# pa_only_1800.net
KiCad netlist of a schematic drawn in EAGLE
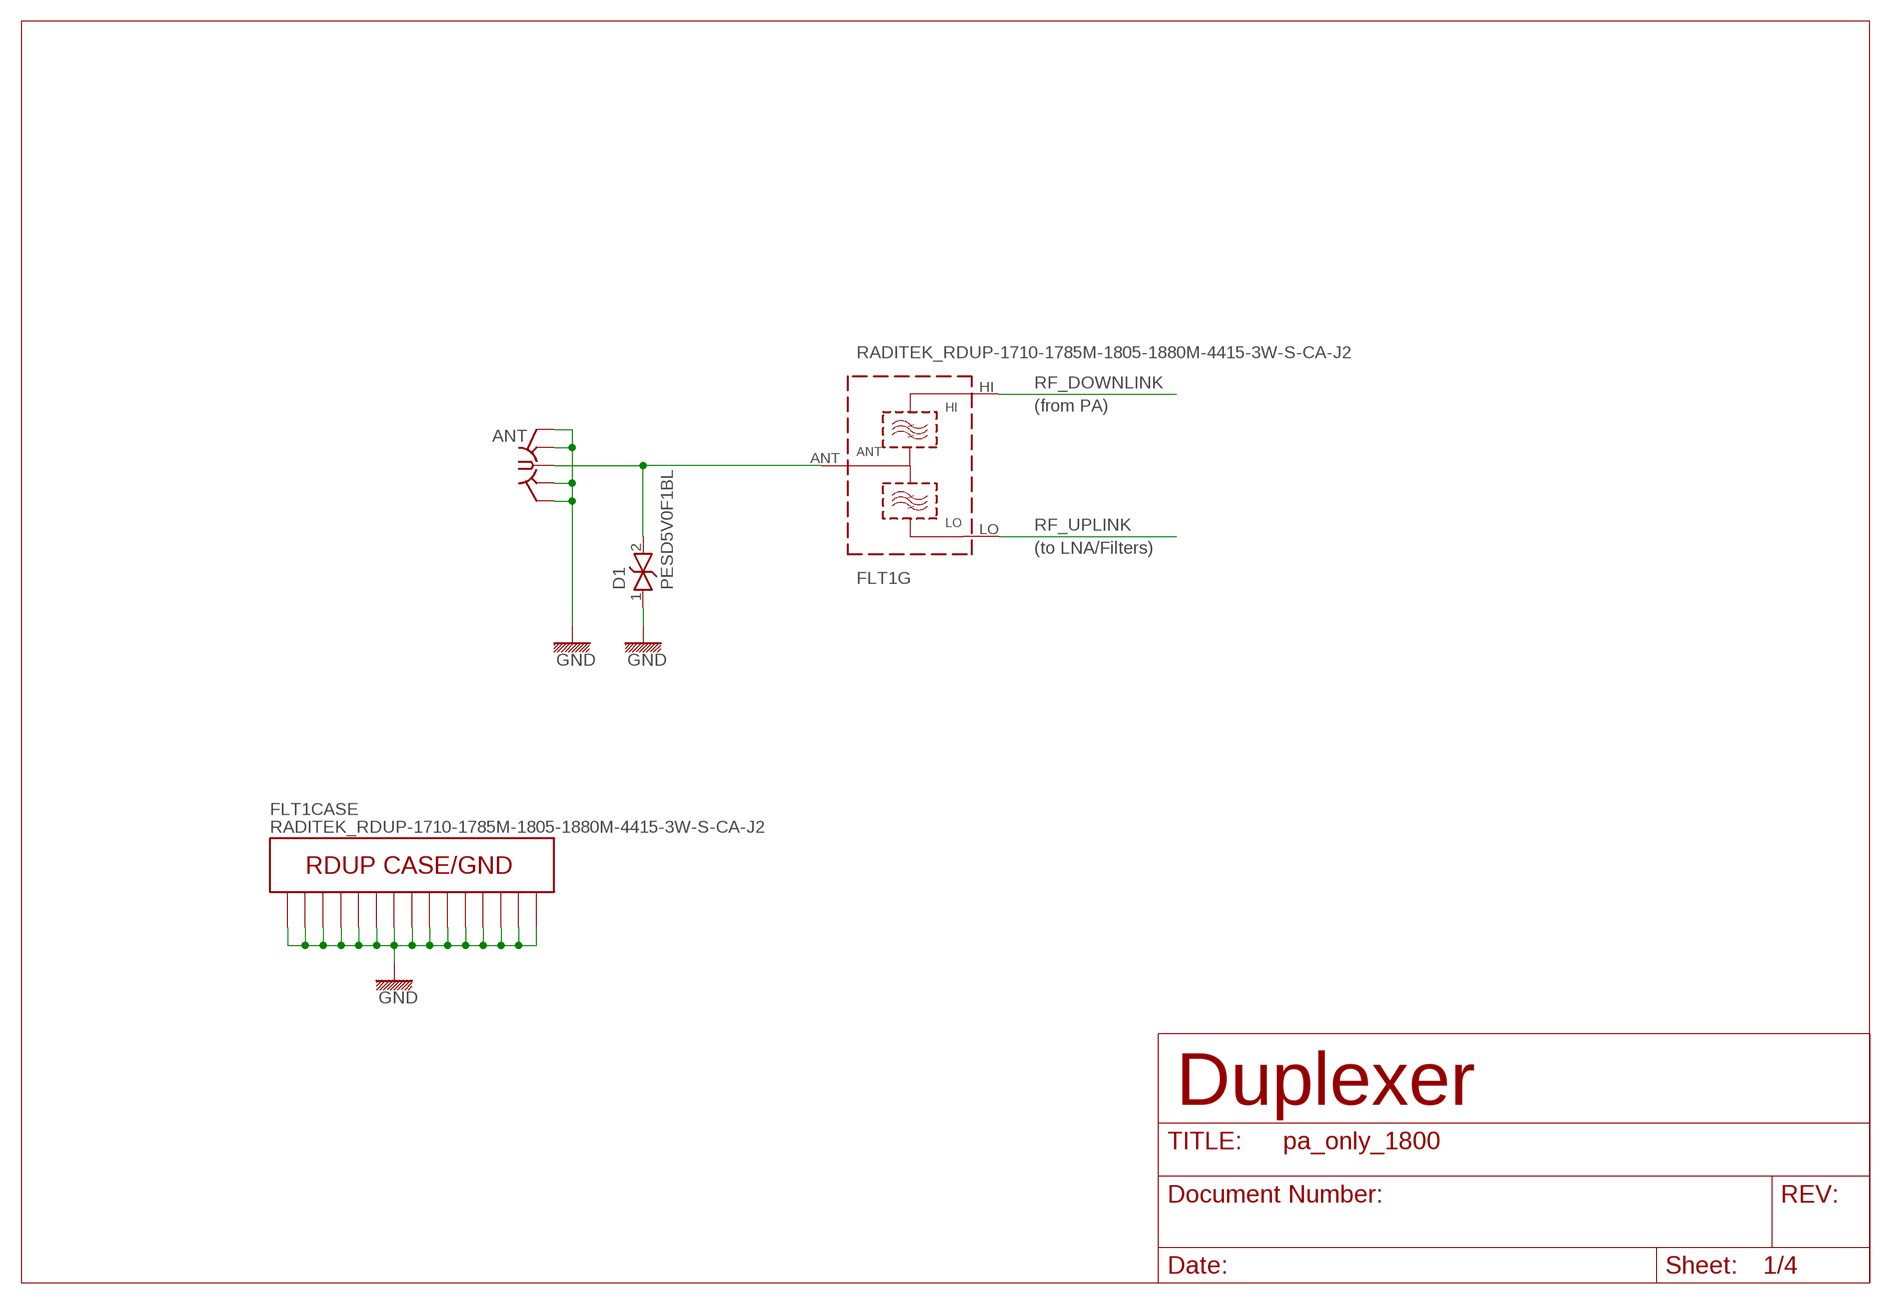
[diagram p0: schematic, sheet 1]
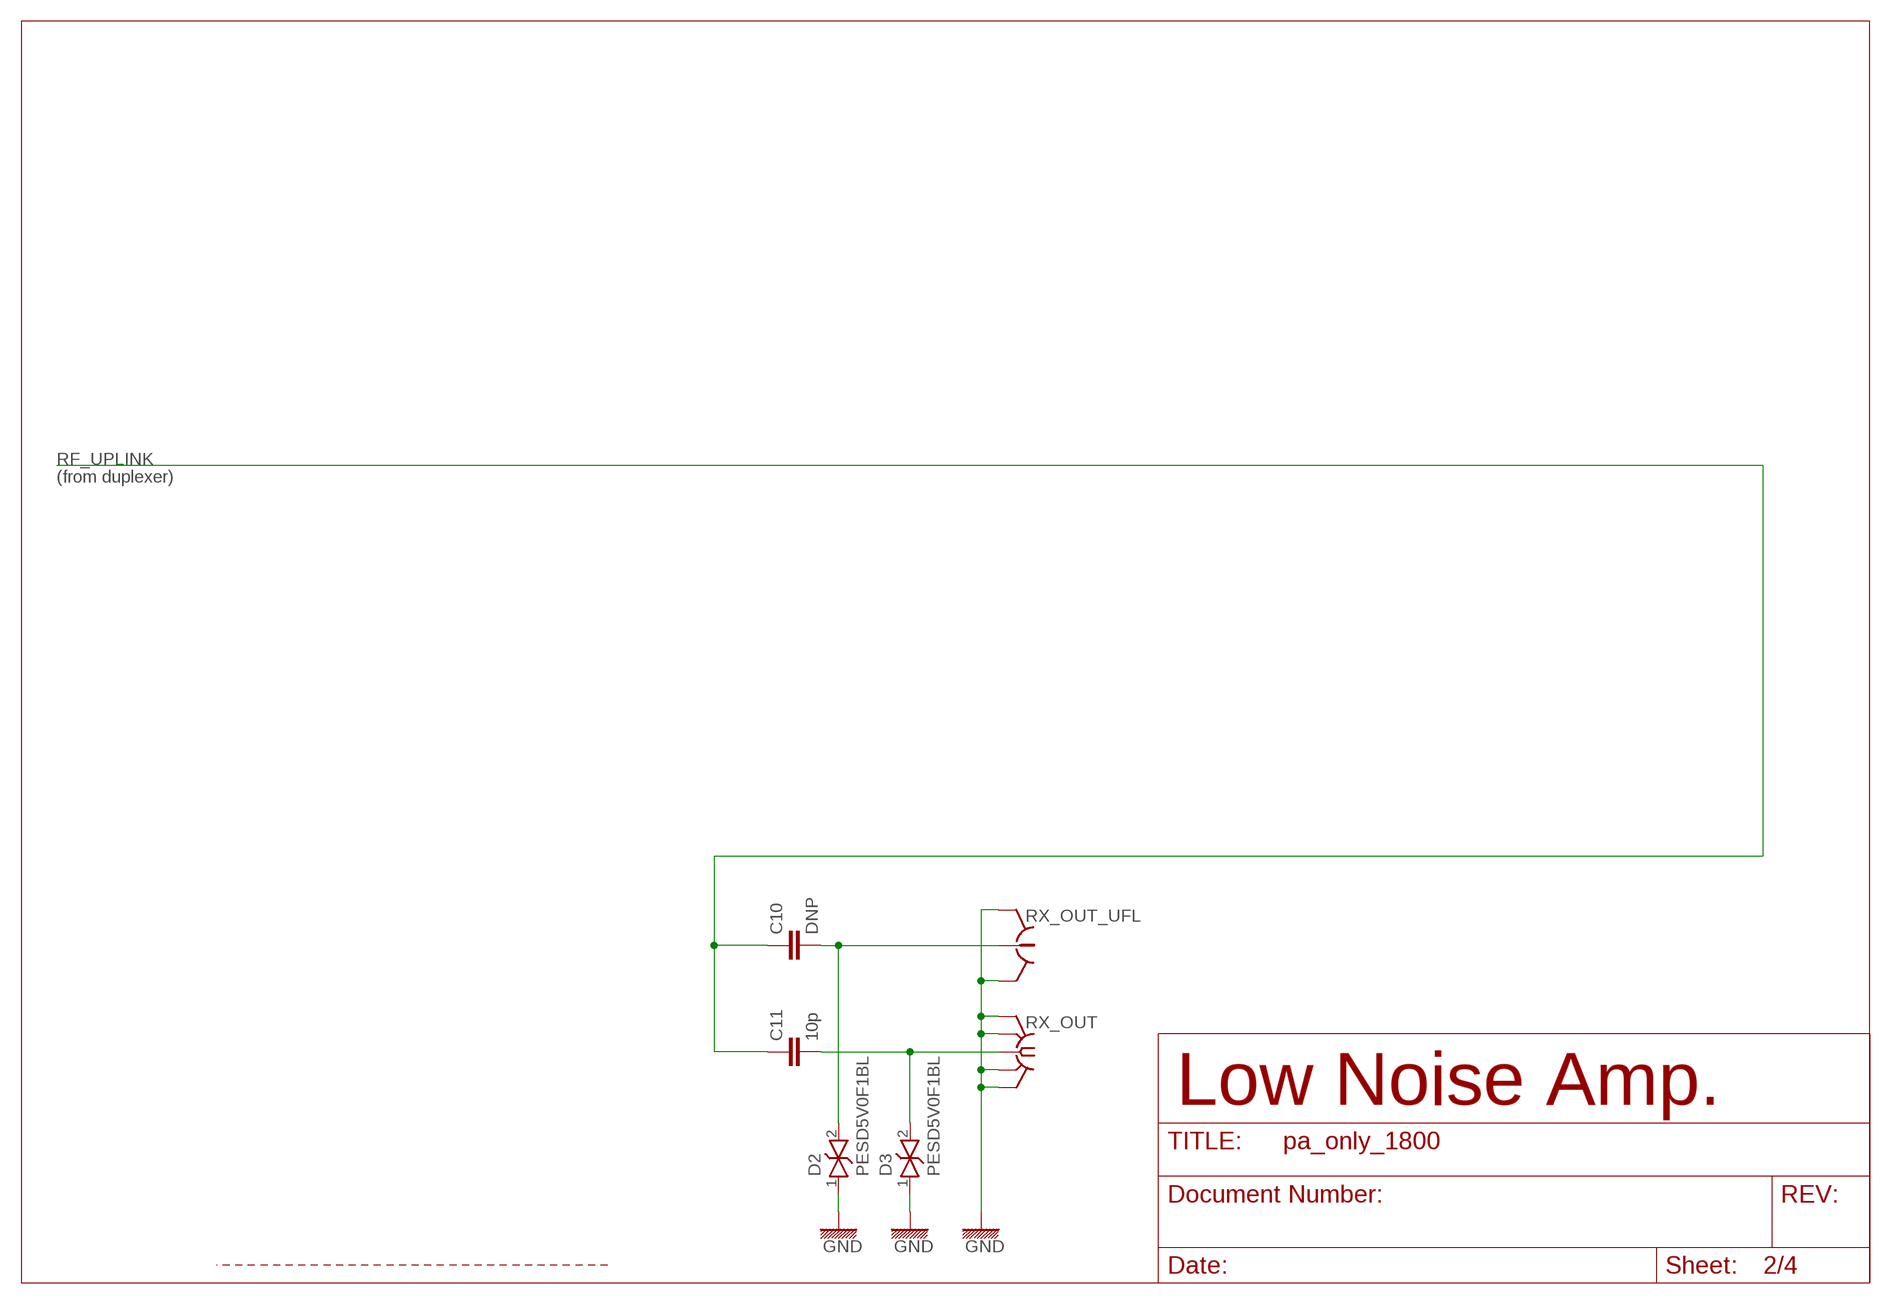
[diagram p1: schematic, sheet 2]
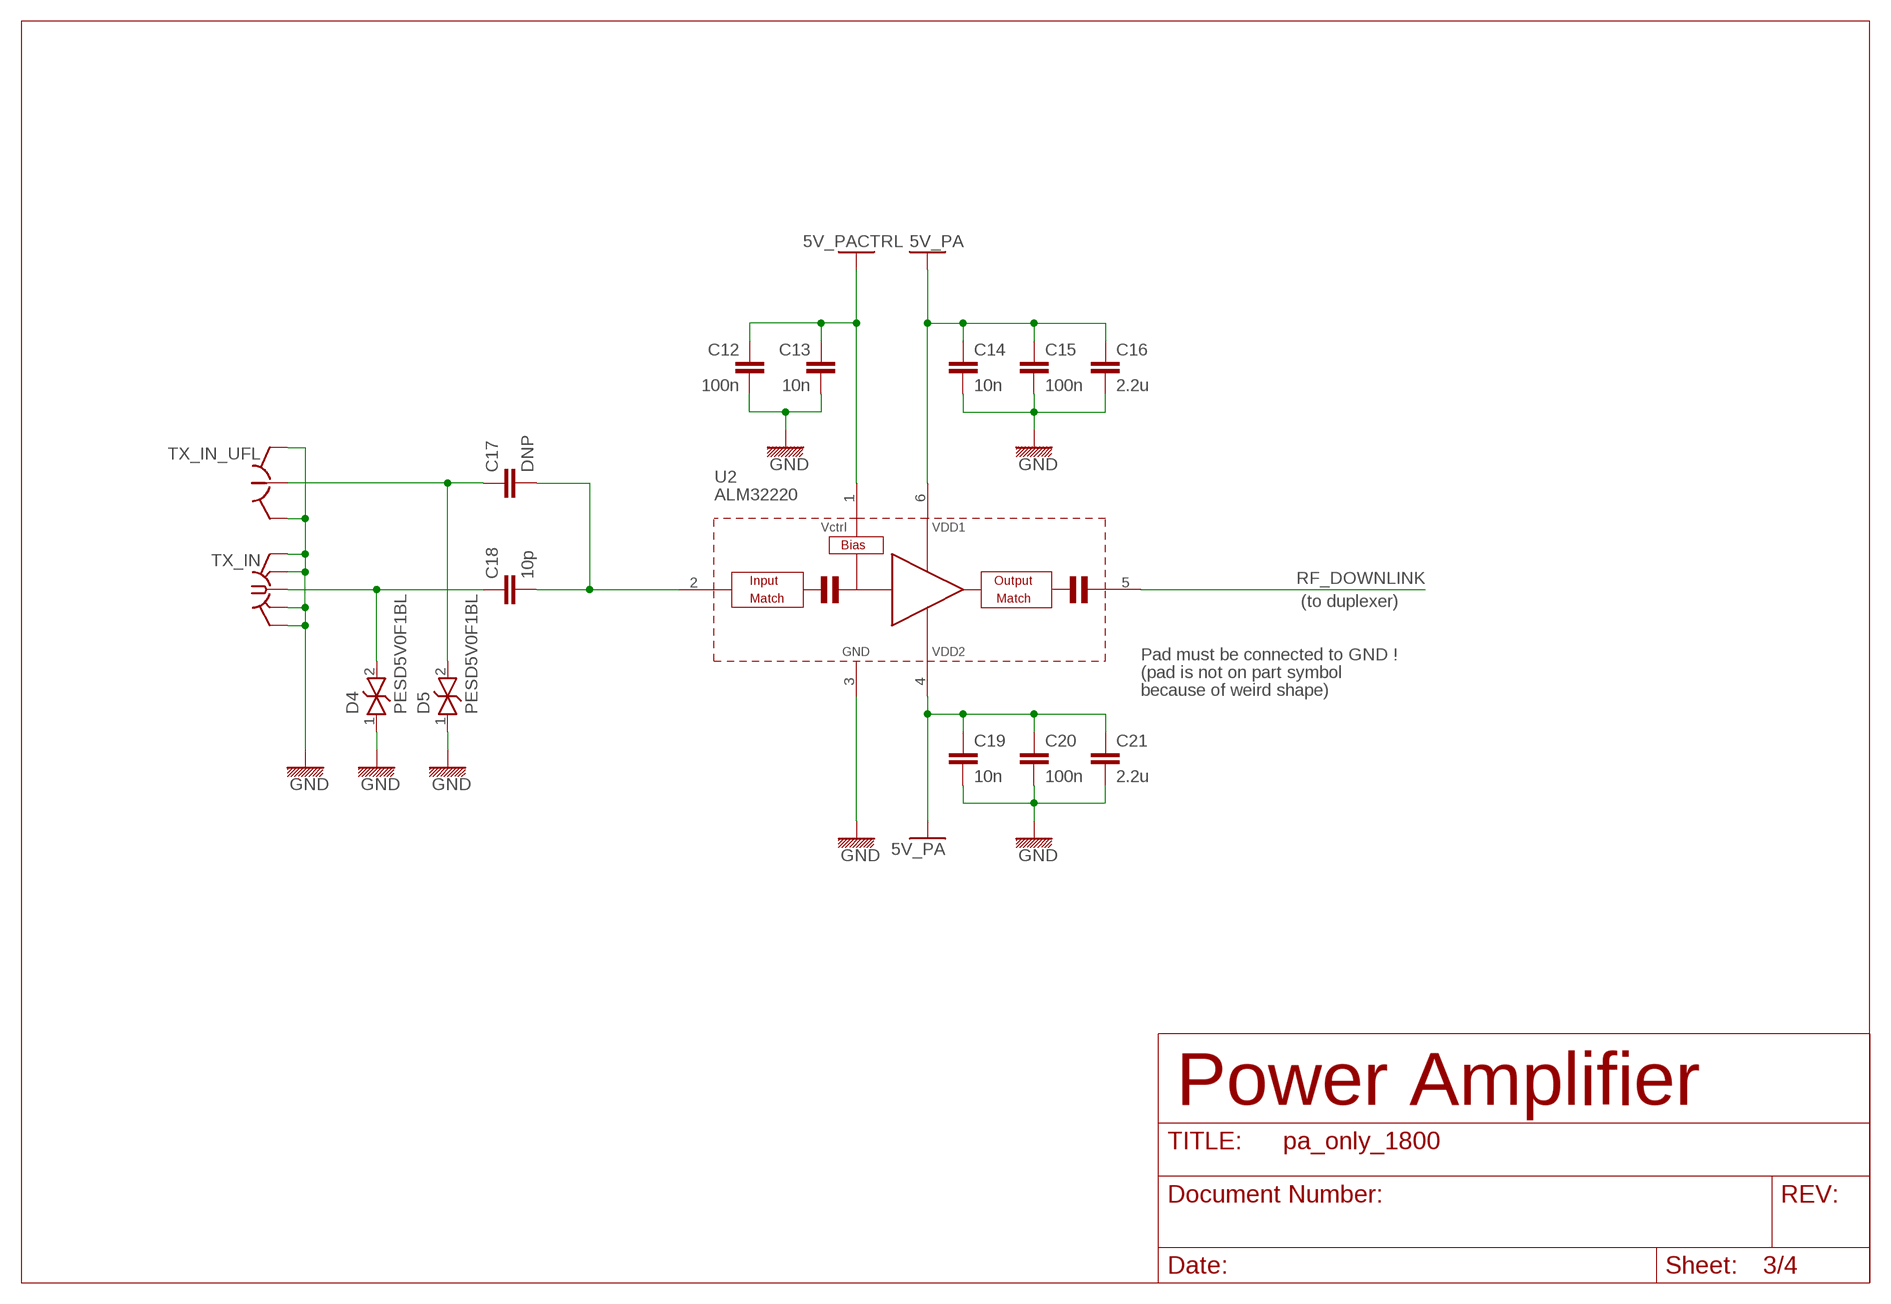
[diagram p2: schematic, sheet 3]
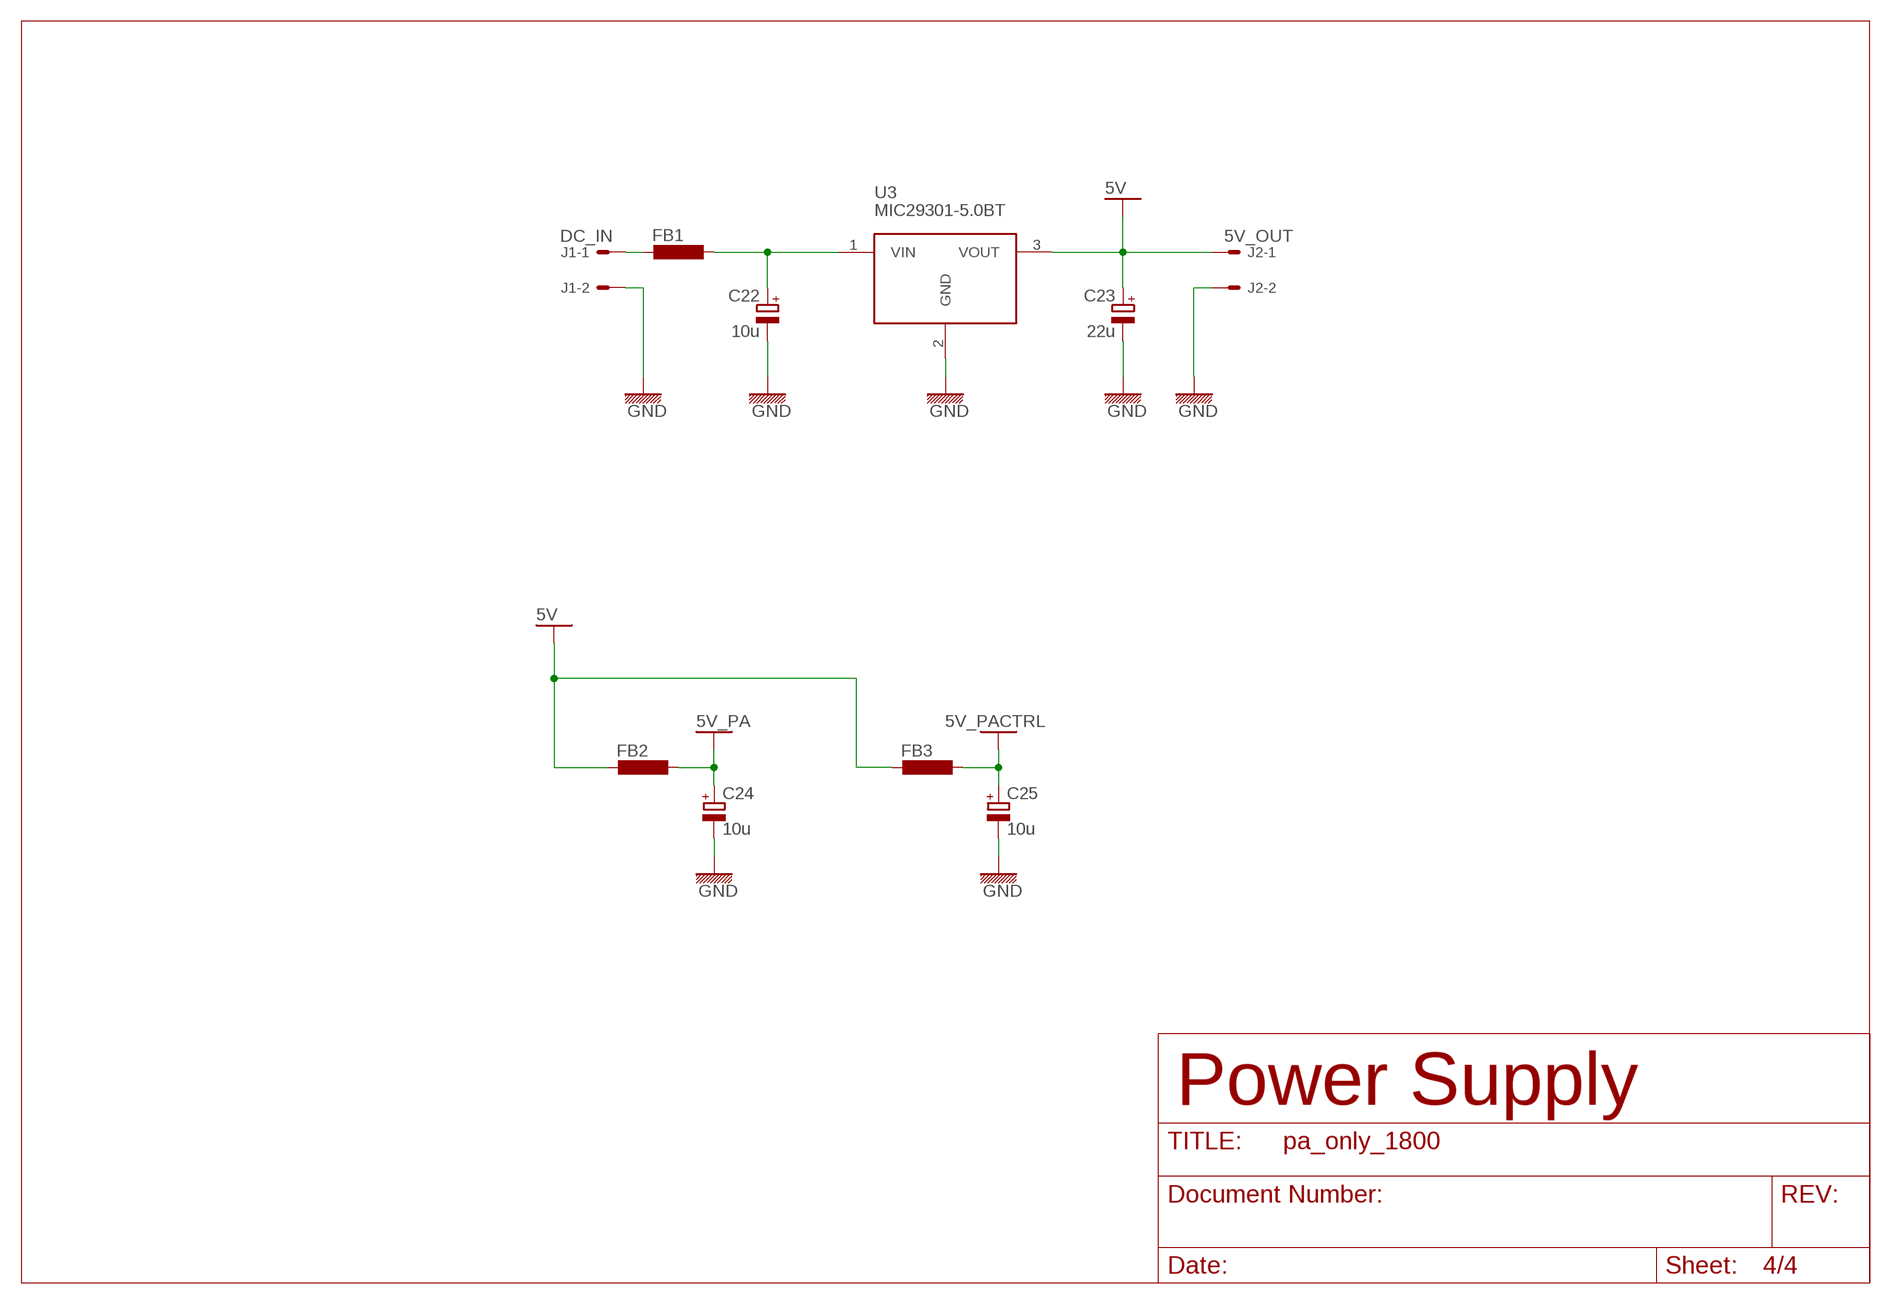
[diagram p3: schematic, sheet 4]

(export (version "E")
  (design (tool "Eeschema 10.0.6"))
  (components
    (comp (ref "ANT")
      (value "SMA-F-S-TH")
      (footprint "eagle-import:SMA-F-S-TH")
      (libsource (lib "eagle-import") (part "SMA-F-S-TH"))
    )
    (comp (ref "D1")
      (value "PESD5V0F1BL")
      (footprint "eagle-import:SOD882")
      (libsource (lib "eagle-import") (part "D_ESD_SOD882"))
    )
    (comp (ref "FLT1")
      (value "RADITEK_RDUP-1710-1785M-1805-1880M-4415-3W-S-CA-J2")
      (footprint "eagle-import:RADITEK_RDUP_4415")
      (libsource (lib "eagle-import") (part "RADITEK_RDUP-1710-1785M-1805-1880M-4415-3W-S-CA-J2"))
    )
    (comp (ref "C22")
      (value "10u")
      (footprint "eagle-import:SMC_A")
      (libsource (lib "eagle-import") (part "CPOL-EUSMCA"))
    )
    (comp (ref "C23")
      (value "22u")
      (footprint "eagle-import:SMC_A")
      (libsource (lib "eagle-import") (part "CPOL-EUSMCA"))
    )
    (comp (ref "C24")
      (value "10u")
      (footprint "eagle-import:SMC_A")
      (libsource (lib "eagle-import") (part "CPOL-EUSMCA"))
    )
    (comp (ref "C25")
      (value "10u")
      (footprint "eagle-import:SMC_A")
      (libsource (lib "eagle-import") (part "CPOL-EUSMCA"))
    )
    (comp (ref "FB1")
      (value "FBEAD_1206")
      (footprint "eagle-import:1206")
      (libsource (lib "eagle-import") (part "FBEAD_1206"))
    )
    (comp (ref "FB2")
      (value "FBEAD_1206")
      (footprint "eagle-import:1206")
      (libsource (lib "eagle-import") (part "FBEAD_1206"))
    )
    (comp (ref "FB3")
      (value "FBEAD_0603")
      (footprint "eagle-import:0603")
      (libsource (lib "eagle-import") (part "FBEAD_0603"))
    )
    (comp (ref "J1")
      (value "DC_IN")
      (footprint "eagle-import:6410-02")
      (libsource (lib "eagle-import") (part "22-?-0227-2021"))
    )
    (comp (ref "J2")
      (value "5V_OUT")
      (footprint "eagle-import:6410-02")
      (fields (field (name "OC_FARNELL") "unknown") (field (name "OC_NEWARK") "unknown"))
      (libsource (lib "eagle-import") (part "22-?-0227-2021"))
    )
    (comp (ref "U3")
      (value "MIC29301-5.0BT")
      (footprint "eagle-import:TO220BV")
      (libsource (lib "eagle-import") (part "MIC29XXX-FIX_WT_TO220BV"))
    )
    (comp (ref "C10")
      (value "DNP")
      (footprint "eagle-import:0603")
      (libsource (lib "eagle-import") (part "C-EU_0603"))
    )
    (comp (ref "C11")
      (value "10p")
      (footprint "eagle-import:0603")
      (libsource (lib "eagle-import") (part "C-EU_0603"))
    )
    (comp (ref "D2")
      (value "PESD5V0F1BL")
      (footprint "eagle-import:SOD882")
      (libsource (lib "eagle-import") (part "D_ESD_SOD882"))
    )
    (comp (ref "D3")
      (value "PESD5V0F1BL")
      (footprint "eagle-import:SOD882")
      (libsource (lib "eagle-import") (part "D_ESD_SOD882"))
    )
    (comp (ref "RX_OUT")
      (value "SMA-F-S-TH")
      (footprint "eagle-import:SMA-F-S-TH")
      (libsource (lib "eagle-import") (part "SMA-F-S-TH"))
    )
    (comp (ref "RX_OUT_UFL")
      (value "HRS_UFL")
      (footprint "eagle-import:HRS_UFL")
      (libsource (lib "eagle-import") (part "HRS_UFL"))
    )
    (comp (ref "C12")
      (value "100n")
      (footprint "eagle-import:0603")
      (libsource (lib "eagle-import") (part "C-EU_0603"))
    )
    (comp (ref "C13")
      (value "10n")
      (footprint "eagle-import:0603")
      (libsource (lib "eagle-import") (part "C-EU_0603"))
    )
    (comp (ref "C14")
      (value "10n")
      (footprint "eagle-import:0603")
      (libsource (lib "eagle-import") (part "C-EU_0603"))
    )
    (comp (ref "C15")
      (value "100n")
      (footprint "eagle-import:0603")
      (libsource (lib "eagle-import") (part "C-EU_0603"))
    )
    (comp (ref "C16")
      (value "2.2u")
      (footprint "eagle-import:0805")
      (libsource (lib "eagle-import") (part "C-EU_0805"))
    )
    (comp (ref "C17")
      (value "DNP")
      (footprint "eagle-import:0603")
      (libsource (lib "eagle-import") (part "C-EU_0603"))
    )
    (comp (ref "C18")
      (value "10p")
      (footprint "eagle-import:0603")
      (libsource (lib "eagle-import") (part "C-EU_0603"))
    )
    (comp (ref "C19")
      (value "10n")
      (footprint "eagle-import:0603")
      (libsource (lib "eagle-import") (part "C-EU_0603"))
    )
    (comp (ref "C20")
      (value "100n")
      (footprint "eagle-import:0603")
      (libsource (lib "eagle-import") (part "C-EU_0603"))
    )
    (comp (ref "C21")
      (value "2.2u")
      (footprint "eagle-import:0805")
      (libsource (lib "eagle-import") (part "C-EU_0805"))
    )
    (comp (ref "D4")
      (value "PESD5V0F1BL")
      (footprint "eagle-import:SOD882")
      (libsource (lib "eagle-import") (part "D_ESD_SOD882"))
    )
    (comp (ref "D5")
      (value "PESD5V0F1BL")
      (footprint "eagle-import:SOD882")
      (libsource (lib "eagle-import") (part "D_ESD_SOD882"))
    )
    (comp (ref "TX_IN")
      (value "SMA-F-S-TH")
      (footprint "eagle-import:SMA-F-S-TH")
      (libsource (lib "eagle-import") (part "SMA-F-S-TH"))
    )
    (comp (ref "TX_IN_UFL")
      (value "HRS_UFL")
      (footprint "eagle-import:HRS_UFL")
      (libsource (lib "eagle-import") (part "HRS_UFL"))
    )
    (comp (ref "U2")
      (value "ALM32220")
      (footprint "eagle-import:ALM32X20")
      (libsource (lib "eagle-import") (part "ALM32220"))
    )
  )
  (nets
    (net (code "1") (name "5V") (class "Default")
      (node (ref "C23") (pin "+") (pinfunction "+_+") (pintype "passive"))
      (node (ref "FB2") (pin "1") (pinfunction "1_1") (pintype "passive"))
      (node (ref "FB3") (pin "1") (pinfunction "1_1") (pintype "passive"))
      (node (ref "J2") (pin "1") (pinfunction "S_1") (pintype "passive"))
      (node (ref "U3") (pin "3") (pinfunction "VOUT_3") (pintype "power_in"))
    )
    (net (code "2") (name "5V_PA") (class "Default")
      (node (ref "C14") (pin "1") (pinfunction "1_1") (pintype "passive"))
      (node (ref "C15") (pin "1") (pinfunction "1_1") (pintype "passive"))
      (node (ref "C16") (pin "1") (pinfunction "1_1") (pintype "passive"))
      (node (ref "C19") (pin "1") (pinfunction "1_1") (pintype "passive"))
      (node (ref "C20") (pin "1") (pinfunction "1_1") (pintype "passive"))
      (node (ref "C21") (pin "1") (pinfunction "1_1") (pintype "passive"))
      (node (ref "C24") (pin "+") (pinfunction "+_+") (pintype "passive"))
      (node (ref "FB2") (pin "2") (pinfunction "2_2") (pintype "passive"))
      (node (ref "U2") (pin "4") (pinfunction "VDD2_4") (pintype "power_in"))
      (node (ref "U2") (pin "6") (pinfunction "VDD1_6") (pintype "power_in"))
    )
    (net (code "3") (name "5V_PACTRL") (class "Default")
      (node (ref "C12") (pin "1") (pinfunction "1_1") (pintype "passive"))
      (node (ref "C13") (pin "1") (pinfunction "1_1") (pintype "passive"))
      (node (ref "C25") (pin "+") (pinfunction "+_+") (pintype "passive"))
      (node (ref "FB3") (pin "2") (pinfunction "2_2") (pintype "passive"))
      (node (ref "U2") (pin "1") (pinfunction "VCTRL_1") (pintype "power_in"))
    )
    (net (code "4") (name "GND") (class "Default")
      (node (ref "ANT") (pin "G1") (pinfunction "GND_G1") (pintype "power_in"))
      (node (ref "ANT") (pin "G2") (pinfunction "GND_G2") (pintype "power_in"))
      (node (ref "ANT") (pin "G3") (pinfunction "GND_G3") (pintype "power_in"))
      (node (ref "ANT") (pin "G4") (pinfunction "GND_G4") (pintype "power_in"))
      (node (ref "C12") (pin "2") (pinfunction "2_2") (pintype "passive"))
      (node (ref "C13") (pin "2") (pinfunction "2_2") (pintype "passive"))
      (node (ref "C14") (pin "2") (pinfunction "2_2") (pintype "passive"))
      (node (ref "C15") (pin "2") (pinfunction "2_2") (pintype "passive"))
      (node (ref "C16") (pin "2") (pinfunction "2_2") (pintype "passive"))
      (node (ref "C19") (pin "2") (pinfunction "2_2") (pintype "passive"))
      (node (ref "C20") (pin "2") (pinfunction "2_2") (pintype "passive"))
      (node (ref "C21") (pin "2") (pinfunction "2_2") (pintype "passive"))
      (node (ref "C22") (pin "-") (pinfunction "-_-") (pintype "passive"))
      (node (ref "C23") (pin "-") (pinfunction "-_-") (pintype "passive"))
      (node (ref "C24") (pin "-") (pinfunction "-_-") (pintype "passive"))
      (node (ref "C25") (pin "-") (pinfunction "-_-") (pintype "passive"))
      (node (ref "D1") (pin "1") (pinfunction "1_1") (pintype "passive"))
      (node (ref "D2") (pin "1") (pinfunction "1_1") (pintype "passive"))
      (node (ref "D3") (pin "1") (pinfunction "1_1") (pintype "passive"))
      (node (ref "D4") (pin "1") (pinfunction "1_1") (pintype "passive"))
      (node (ref "D5") (pin "1") (pinfunction "1_1") (pintype "passive"))
      (node (ref "FLT1") (pin "GND@1") (pinfunction "GND_GND@1") (pintype "power_in"))
      (node (ref "FLT1") (pin "GND@10") (pinfunction "GND_GND@10") (pintype "power_in"))
      (node (ref "FLT1") (pin "GND@11") (pinfunction "GND_GND@11") (pintype "power_in"))
      (node (ref "FLT1") (pin "GND@12") (pinfunction "GND_GND@12") (pintype "power_in"))
      (node (ref "FLT1") (pin "GND@13") (pinfunction "GND_GND@13") (pintype "power_in"))
      (node (ref "FLT1") (pin "GND@14") (pinfunction "GND_GND@14") (pintype "power_in"))
      (node (ref "FLT1") (pin "GND@15") (pinfunction "GND_GND@15") (pintype "power_in"))
      (node (ref "FLT1") (pin "GND@2") (pinfunction "GND_GND@2") (pintype "power_in"))
      (node (ref "FLT1") (pin "GND@3") (pinfunction "GND_GND@3") (pintype "power_in"))
      (node (ref "FLT1") (pin "GND@4") (pinfunction "GND_GND@4") (pintype "power_in"))
      (node (ref "FLT1") (pin "GND@5") (pinfunction "GND_GND@5") (pintype "power_in"))
      (node (ref "FLT1") (pin "GND@6") (pinfunction "GND_GND@6") (pintype "power_in"))
      (node (ref "FLT1") (pin "GND@7") (pinfunction "GND_GND@7") (pintype "power_in"))
      (node (ref "FLT1") (pin "GND@8") (pinfunction "GND_GND@8") (pintype "power_in"))
      (node (ref "FLT1") (pin "GND@9") (pinfunction "GND_GND@9") (pintype "power_in"))
      (node (ref "J1") (pin "2") (pinfunction "S_2") (pintype "passive"))
      (node (ref "J2") (pin "2") (pinfunction "S_2") (pintype "passive"))
      (node (ref "RX_OUT") (pin "G1") (pinfunction "GND_G1") (pintype "power_in"))
      (node (ref "RX_OUT") (pin "G2") (pinfunction "GND_G2") (pintype "power_in"))
      (node (ref "RX_OUT") (pin "G3") (pinfunction "GND_G3") (pintype "power_in"))
      (node (ref "RX_OUT") (pin "G4") (pinfunction "GND_G4") (pintype "power_in"))
      (node (ref "RX_OUT_UFL") (pin "GND@1") (pinfunction "GND_GND@1") (pintype "power_in"))
      (node (ref "RX_OUT_UFL") (pin "GND@2") (pinfunction "GND_GND@2") (pintype "power_in"))
      (node (ref "TX_IN") (pin "G1") (pinfunction "GND_G1") (pintype "power_in"))
      (node (ref "TX_IN") (pin "G2") (pinfunction "GND_G2") (pintype "power_in"))
      (node (ref "TX_IN") (pin "G3") (pinfunction "GND_G3") (pintype "power_in"))
      (node (ref "TX_IN") (pin "G4") (pinfunction "GND_G4") (pintype "power_in"))
      (node (ref "TX_IN_UFL") (pin "GND@1") (pinfunction "GND_GND@1") (pintype "power_in"))
      (node (ref "TX_IN_UFL") (pin "GND@2") (pinfunction "GND_GND@2") (pintype "power_in"))
      (node (ref "U2") (pin "3") (pinfunction "GND_3") (pintype "power_in"))
      (node (ref "U3") (pin "2") (pinfunction "GND_2") (pintype "power_in"))
    )
    (net (code "5") (name "Net-(ANT-1)") (class "Default")
      (node (ref "ANT") (pin "C") (pinfunction "1_C") (pintype "passive"))
      (node (ref "D1") (pin "2") (pinfunction "2_2") (pintype "passive"))
      (node (ref "FLT1") (pin "ANT") (pinfunction "ANT_ANT") (pintype "passive"))
    )
    (net (code "6") (name "Net-(J1A-S)") (class "Default")
      (node (ref "FB1") (pin "1") (pinfunction "1_1") (pintype "passive"))
      (node (ref "J1") (pin "1") (pinfunction "S_1") (pintype "passive"))
    )
    (net (code "7") (name "Net-(RX_OUT-1)") (class "Default")
      (node (ref "C11") (pin "2") (pinfunction "2_2") (pintype "passive"))
      (node (ref "D3") (pin "2") (pinfunction "2_2") (pintype "passive"))
      (node (ref "RX_OUT") (pin "C") (pinfunction "1_C") (pintype "passive"))
    )
    (net (code "8") (name "Net-(RX_OUT_UFL-1)") (class "Default")
      (node (ref "C10") (pin "2") (pinfunction "2_2") (pintype "passive"))
      (node (ref "D2") (pin "2") (pinfunction "2_2") (pintype "passive"))
      (node (ref "RX_OUT_UFL") (pin "SIG") (pinfunction "1_SIG") (pintype "passive"))
    )
    (net (code "9") (name "Net-(TX_IN-1)") (class "Default")
      (node (ref "C18") (pin "1") (pinfunction "1_1") (pintype "passive"))
      (node (ref "D4") (pin "2") (pinfunction "2_2") (pintype "passive"))
      (node (ref "TX_IN") (pin "C") (pinfunction "1_C") (pintype "passive"))
    )
    (net (code "10") (name "Net-(TX_IN_UFL-1)") (class "Default")
      (node (ref "C17") (pin "1") (pinfunction "1_1") (pintype "passive"))
      (node (ref "D5") (pin "2") (pinfunction "2_2") (pintype "passive"))
      (node (ref "TX_IN_UFL") (pin "SIG") (pinfunction "1_SIG") (pintype "passive"))
    )
    (net (code "11") (name "Net-(U2-RF_IN)") (class "Default")
      (node (ref "C17") (pin "2") (pinfunction "2_2") (pintype "passive"))
      (node (ref "C18") (pin "2") (pinfunction "2_2") (pintype "passive"))
      (node (ref "U2") (pin "2") (pinfunction "RF_IN_2") (pintype "input"))
    )
    (net (code "12") (name "Net-(U3-VIN)") (class "Default")
      (node (ref "C22") (pin "+") (pinfunction "+_+") (pintype "passive"))
      (node (ref "FB1") (pin "2") (pinfunction "2_2") (pintype "passive"))
      (node (ref "U3") (pin "1") (pinfunction "VIN_1") (pintype "power_in"))
    )
    (net (code "13") (name "RF_DOWNLINK") (class "Default")
      (node (ref "FLT1") (pin "HI") (pinfunction "HI_HI") (pintype "passive"))
      (node (ref "U2") (pin "5") (pinfunction "RF_OUT_5") (pintype "output"))
    )
    (net (code "14") (name "RF_UPLINK") (class "Default")
      (node (ref "C10") (pin "1") (pinfunction "1_1") (pintype "passive"))
      (node (ref "C11") (pin "1") (pinfunction "1_1") (pintype "passive"))
      (node (ref "FLT1") (pin "LO") (pinfunction "LO_LO") (pintype "passive"))
    )
  )
)
